# Pic32BB.net
KiCad netlist of a schematic drawn in EAGLE
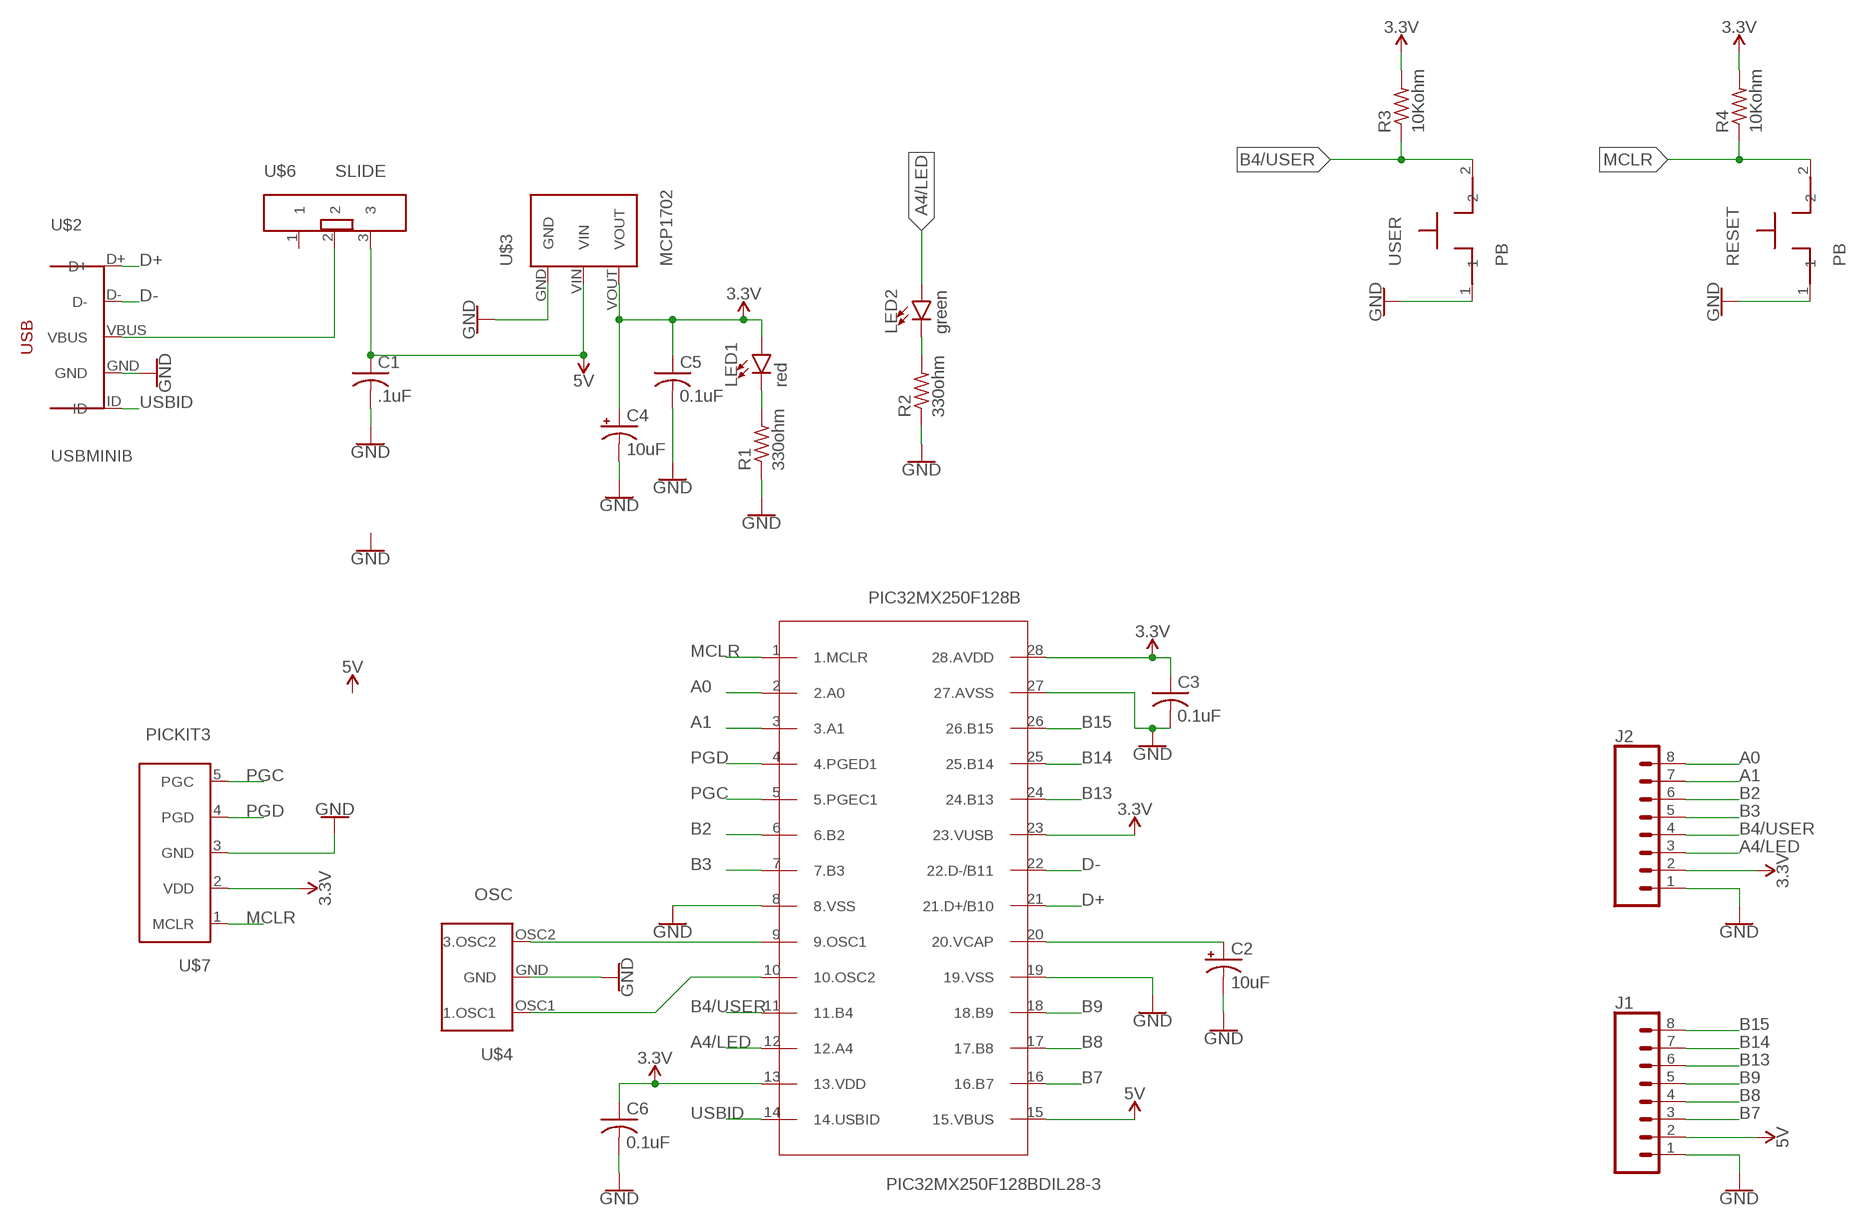
[diagram p0: schematic, sheet 1]

(export (version "E")
  (design (tool "Eeschema 10.0.6"))
  (components
    (comp (ref "C1")
      (value ".1uF")
      (footprint "eagle-import:C025-025X050")
      (libsource (lib "eagle-import") (part "C-US025-025X050"))
    )
    (comp (ref "C2")
      (value "10uF")
      (footprint "eagle-import:B45181B")
      (libsource (lib "eagle-import") (part "CPOL-USB45181B"))
    )
    (comp (ref "C3")
      (value "0.1uF")
      (footprint "eagle-import:C025-025X050")
      (libsource (lib "eagle-import") (part "C-US025-025X050"))
    )
    (comp (ref "C4")
      (value "10uF")
      (footprint "eagle-import:B45181B")
      (libsource (lib "eagle-import") (part "CPOL-USB45181B"))
    )
    (comp (ref "C5")
      (value "0.1uF")
      (footprint "eagle-import:C025-025X050")
      (libsource (lib "eagle-import") (part "C-US025-025X050"))
    )
    (comp (ref "C6")
      (value "0.1uF")
      (footprint "eagle-import:C025-025X050")
      (libsource (lib "eagle-import") (part "C-US025-025X050"))
    )
    (comp (ref "J1")
      (value "CONN_08\"")
      (footprint "eagle-import:1X08")
      (libsource (lib "eagle-import") (part "CONN_08{dblquote}"))
    )
    (comp (ref "J2")
      (value "CONN_08\"")
      (footprint "eagle-import:1X08")
      (libsource (lib "eagle-import") (part "CONN_08{dblquote}"))
    )
    (comp (ref "LED1")
      (value "red")
      (footprint "eagle-import:LED_3MM")
      (libsource (lib "eagle-import") (part "LED3MM"))
    )
    (comp (ref "LED2")
      (value "green")
      (footprint "eagle-import:LED_3MM")
      (libsource (lib "eagle-import") (part "LED3MM"))
    )
    (comp (ref "PIC32MX250F128B")
      (value "PIC32MX250F128BDIL28-3")
      (footprint "eagle-import:DIL28-3")
      (libsource (lib "eagle-import") (part "PIC32MX250F128BDIL28-3"))
    )
    (comp (ref "R1")
      (value "330ohm")
      (footprint "eagle-import:0207_10")
      (libsource (lib "eagle-import") (part "R-US_0207/10"))
    )
    (comp (ref "R2")
      (value "330ohm")
      (footprint "eagle-import:0207_10")
      (libsource (lib "eagle-import") (part "R-US_0207/10"))
    )
    (comp (ref "R3")
      (value "10Kohm")
      (footprint "eagle-import:0207_10")
      (libsource (lib "eagle-import") (part "R-US_0207/10"))
    )
    (comp (ref "R4")
      (value "10Kohm")
      (footprint "eagle-import:0207_10")
      (libsource (lib "eagle-import") (part "R-US_0207/10"))
    )
    (comp (ref "RESET")
      (value "PB")
      (footprint "eagle-import:PB")
      (libsource (lib "eagle-import") (part "PB"))
    )
    (comp (ref "U$2")
      (value "USBMINIB")
      (footprint "eagle-import:USB-MB-H")
      (libsource (lib "eagle-import") (part "USBMINIB"))
    )
    (comp (ref "U$3")
      (value "MCP1702")
      (footprint "eagle-import:TO92")
      (libsource (lib "eagle-import") (part "MCP1702"))
    )
    (comp (ref "U$4")
      (value "OSC")
      (footprint "eagle-import:OSC")
      (libsource (lib "eagle-import") (part "OSC"))
    )
    (comp (ref "U$6")
      (value "SLIDE")
      (footprint "eagle-import:SLIDE")
      (libsource (lib "eagle-import") (part "SLIDE"))
    )
    (comp (ref "U$7")
      (value "PICKIT3")
      (footprint "eagle-import:PICKIT3")
      (libsource (lib "eagle-import") (part "PICKIT3"))
    )
    (comp (ref "USER")
      (value "PB")
      (footprint "eagle-import:PB")
      (libsource (lib "eagle-import") (part "PB"))
    )
  )
  (nets
    (net (code "1") (name "/A0") (class "Default")
      (node (ref "J2") (pin "8") (pinfunction "8_8") (pintype "passive"))
      (node (ref "PIC32MX250F128B") (pin "2") (pinfunction "2.A0_2") (pintype "bidirectional"))
    )
    (net (code "2") (name "/A1") (class "Default")
      (node (ref "J2") (pin "7") (pinfunction "7_7") (pintype "passive"))
      (node (ref "PIC32MX250F128B") (pin "3") (pinfunction "3.A1_3") (pintype "bidirectional"))
    )
    (net (code "3") (name "/B2") (class "Default")
      (node (ref "J2") (pin "6") (pinfunction "6_6") (pintype "passive"))
      (node (ref "PIC32MX250F128B") (pin "6") (pinfunction "6.B2_6") (pintype "bidirectional"))
    )
    (net (code "4") (name "/B3") (class "Default")
      (node (ref "J2") (pin "5") (pinfunction "5_5") (pintype "passive"))
      (node (ref "PIC32MX250F128B") (pin "7") (pinfunction "7.B3_7") (pintype "bidirectional"))
    )
    (net (code "5") (name "/B7") (class "Default")
      (node (ref "J1") (pin "3") (pinfunction "3_3") (pintype "passive"))
      (node (ref "PIC32MX250F128B") (pin "16") (pinfunction "16.B7_16") (pintype "bidirectional"))
    )
    (net (code "6") (name "/B8") (class "Default")
      (node (ref "J1") (pin "4") (pinfunction "4_4") (pintype "passive"))
      (node (ref "PIC32MX250F128B") (pin "17") (pinfunction "17.B8_17") (pintype "bidirectional"))
    )
    (net (code "7") (name "/B9") (class "Default")
      (node (ref "J1") (pin "5") (pinfunction "5_5") (pintype "passive"))
      (node (ref "PIC32MX250F128B") (pin "18") (pinfunction "18.B9_18") (pintype "bidirectional"))
    )
    (net (code "8") (name "/B13") (class "Default")
      (node (ref "J1") (pin "6") (pinfunction "6_6") (pintype "passive"))
      (node (ref "PIC32MX250F128B") (pin "24") (pinfunction "24.B13_24") (pintype "bidirectional"))
    )
    (net (code "9") (name "/B14") (class "Default")
      (node (ref "J1") (pin "7") (pinfunction "7_7") (pintype "passive"))
      (node (ref "PIC32MX250F128B") (pin "25") (pinfunction "25.B14_25") (pintype "bidirectional"))
    )
    (net (code "10") (name "/B15") (class "Default")
      (node (ref "J1") (pin "8") (pinfunction "8_8") (pintype "passive"))
      (node (ref "PIC32MX250F128B") (pin "26") (pinfunction "26.B15_26") (pintype "bidirectional"))
    )
    (net (code "11") (name "/D+") (class "Default")
      (node (ref "PIC32MX250F128B") (pin "21") (pinfunction "21.D+/B10_21") (pintype "bidirectional"))
      (node (ref "U$2") (pin "D+") (pinfunction "D+_D+") (pintype "bidirectional"))
    )
    (net (code "12") (name "/D-") (class "Default")
      (node (ref "PIC32MX250F128B") (pin "22") (pinfunction "22.D-/B11_22") (pintype "bidirectional"))
      (node (ref "U$2") (pin "D-") (pinfunction "D-_D-") (pintype "bidirectional"))
    )
    (net (code "13") (name "/PGC") (class "Default")
      (node (ref "PIC32MX250F128B") (pin "5") (pinfunction "5.PGEC1_5") (pintype "bidirectional"))
      (node (ref "U$7") (pin "5") (pinfunction "PGC_5") (pintype "bidirectional"))
    )
    (net (code "14") (name "/PGD") (class "Default")
      (node (ref "PIC32MX250F128B") (pin "4") (pinfunction "4.PGED1_4") (pintype "bidirectional"))
      (node (ref "U$7") (pin "4") (pinfunction "PGD_4") (pintype "bidirectional"))
    )
    (net (code "15") (name "/USBID") (class "Default")
      (node (ref "PIC32MX250F128B") (pin "14") (pinfunction "14.USBID_14") (pintype "bidirectional"))
      (node (ref "U$2") (pin "ID") (pinfunction "ID_ID") (pintype "bidirectional"))
    )
    (net (code "16") (name "3.3V") (class "Default")
      (node (ref "C3") (pin "1") (pinfunction "1_1") (pintype "passive"))
      (node (ref "C4") (pin "+") (pinfunction "+_+") (pintype "passive"))
      (node (ref "C5") (pin "1") (pinfunction "1_1") (pintype "passive"))
      (node (ref "C6") (pin "1") (pinfunction "1_1") (pintype "passive"))
      (node (ref "J2") (pin "2") (pinfunction "2_2") (pintype "passive"))
      (node (ref "LED1") (pin "A") (pinfunction "A_A") (pintype "passive"))
      (node (ref "PIC32MX250F128B") (pin "13") (pinfunction "13.VDD_13") (pintype "bidirectional"))
      (node (ref "PIC32MX250F128B") (pin "23") (pinfunction "23.VUSB_23") (pintype "bidirectional"))
      (node (ref "PIC32MX250F128B") (pin "28") (pinfunction "28.AVDD_28") (pintype "bidirectional"))
      (node (ref "R3") (pin "2") (pinfunction "2_2") (pintype "passive"))
      (node (ref "R4") (pin "2") (pinfunction "2_2") (pintype "passive"))
      (node (ref "U$3") (pin "VOUT") (pinfunction "VOUT_VOUT") (pintype "bidirectional"))
      (node (ref "U$7") (pin "2") (pinfunction "VDD_2") (pintype "bidirectional"))
    )
    (net (code "17") (name "5V") (class "Default")
      (node (ref "C1") (pin "1") (pinfunction "1_1") (pintype "passive"))
      (node (ref "J1") (pin "2") (pinfunction "2_2") (pintype "passive"))
      (node (ref "PIC32MX250F128B") (pin "15") (pinfunction "15.VBUS_15") (pintype "bidirectional"))
      (node (ref "U$3") (pin "VIN") (pinfunction "VIN_VIN") (pintype "bidirectional"))
      (node (ref "U$6") (pin "3") (pinfunction "3_3") (pintype "bidirectional"))
    )
    (net (code "18") (name "A4{slash}LED") (class "Default")
      (node (ref "J2") (pin "3") (pinfunction "3_3") (pintype "passive"))
      (node (ref "LED2") (pin "A") (pinfunction "A_A") (pintype "passive"))
      (node (ref "PIC32MX250F128B") (pin "12") (pinfunction "12.A4_12") (pintype "bidirectional"))
    )
    (net (code "19") (name "B4{slash}USER") (class "Default")
      (node (ref "J2") (pin "4") (pinfunction "4_4") (pintype "passive"))
      (node (ref "PIC32MX250F128B") (pin "11") (pinfunction "11.B4_11") (pintype "bidirectional"))
      (node (ref "R3") (pin "1") (pinfunction "1_1") (pintype "passive"))
      (node (ref "USER") (pin "2") (pinfunction "2_2") (pintype "bidirectional"))
    )
    (net (code "20") (name "GND") (class "Default")
      (node (ref "C1") (pin "2") (pinfunction "2_2") (pintype "passive"))
      (node (ref "C2") (pin "-") (pinfunction "-_-") (pintype "passive"))
      (node (ref "C3") (pin "2") (pinfunction "2_2") (pintype "passive"))
      (node (ref "C4") (pin "-") (pinfunction "-_-") (pintype "passive"))
      (node (ref "C5") (pin "2") (pinfunction "2_2") (pintype "passive"))
      (node (ref "C6") (pin "2") (pinfunction "2_2") (pintype "passive"))
      (node (ref "J1") (pin "1") (pinfunction "1_1") (pintype "passive"))
      (node (ref "J2") (pin "1") (pinfunction "1_1") (pintype "passive"))
      (node (ref "PIC32MX250F128B") (pin "19") (pinfunction "19.VSS_19") (pintype "bidirectional"))
      (node (ref "PIC32MX250F128B") (pin "27") (pinfunction "27.AVSS_27") (pintype "bidirectional"))
      (node (ref "PIC32MX250F128B") (pin "8") (pinfunction "8.VSS_8") (pintype "bidirectional"))
      (node (ref "R1") (pin "1") (pinfunction "1_1") (pintype "passive"))
      (node (ref "R2") (pin "1") (pinfunction "1_1") (pintype "passive"))
      (node (ref "RESET") (pin "1") (pinfunction "1_1") (pintype "bidirectional"))
      (node (ref "U$2") (pin "GND") (pinfunction "GND_GND") (pintype "bidirectional"))
      (node (ref "U$3") (pin "GND") (pinfunction "GND_GND") (pintype "bidirectional"))
      (node (ref "U$4") (pin "GND") (pinfunction "GND_GND") (pintype "bidirectional"))
      (node (ref "U$7") (pin "3") (pinfunction "GND_3") (pintype "bidirectional"))
      (node (ref "USER") (pin "1") (pinfunction "1_1") (pintype "bidirectional"))
    )
    (net (code "21") (name "MCLR") (class "Default")
      (node (ref "PIC32MX250F128B") (pin "1") (pinfunction "1.MCLR_1") (pintype "bidirectional"))
      (node (ref "R4") (pin "1") (pinfunction "1_1") (pintype "passive"))
      (node (ref "RESET") (pin "2") (pinfunction "2_2") (pintype "bidirectional"))
      (node (ref "U$7") (pin "1") (pinfunction "MCLR_1") (pintype "bidirectional"))
    )
    (net (code "22") (name "Net-(LED1-C)") (class "Default")
      (node (ref "LED1") (pin "K") (pinfunction "C_K") (pintype "passive"))
      (node (ref "R1") (pin "2") (pinfunction "2_2") (pintype "passive"))
    )
    (net (code "23") (name "Net-(LED2-C)") (class "Default")
      (node (ref "LED2") (pin "K") (pinfunction "C_K") (pintype "passive"))
      (node (ref "R2") (pin "2") (pinfunction "2_2") (pintype "passive"))
    )
    (net (code "24") (name "Net-(PIC32MX250F128B-9.OSC1)") (class "Default")
      (node (ref "PIC32MX250F128B") (pin "9") (pinfunction "9.OSC1_9") (pintype "bidirectional"))
      (node (ref "U$4") (pin "OSC2") (pinfunction "3.OSC2_OSC2") (pintype "bidirectional"))
    )
    (net (code "25") (name "Net-(PIC32MX250F128B-10.OSC2)") (class "Default")
      (node (ref "PIC32MX250F128B") (pin "10") (pinfunction "10.OSC2_10") (pintype "bidirectional"))
      (node (ref "U$4") (pin "OSC1") (pinfunction "1.OSC1_OSC1") (pintype "bidirectional"))
    )
    (net (code "26") (name "Net-(PIC32MX250F128B-20.VCAP)") (class "Default")
      (node (ref "C2") (pin "+") (pinfunction "+_+") (pintype "passive"))
      (node (ref "PIC32MX250F128B") (pin "20") (pinfunction "20.VCAP_20") (pintype "bidirectional"))
    )
    (net (code "27") (name "Net-(U$2-PadVBUS)") (class "Default")
      (node (ref "U$2") (pin "VBUS") (pinfunction "VBUS_VBUS") (pintype "bidirectional"))
      (node (ref "U$6") (pin "2") (pinfunction "2_2") (pintype "bidirectional"))
    )
    (net (code "28") (name "unconnected-(U$6-Pad1)") (class "Default")
      (node (ref "U$6") (pin "1") (pinfunction "1_1") (pintype "bidirectional"))
    )
  )
)
